# LM358.net
KiCad netlist of a schematic drawn in Altium Designer
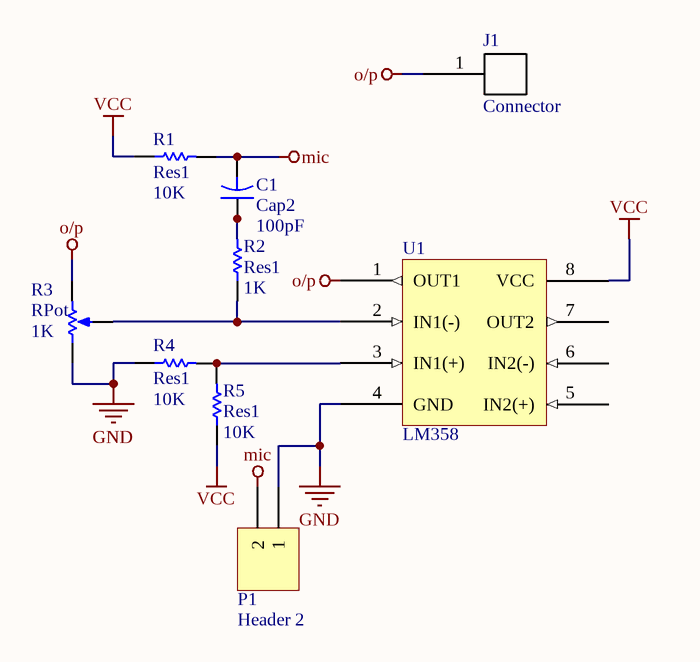
[diagram p0: LM358.SchDoc]

(export (version "E")
  (design (tool "Eeschema 10.0.6"))
  (components
    (comp (ref "C1")
      (value "Cap2")
      (footprint "CAPR5-4X5")
      (description "Capacitor")
      (fields (field (name "ALTIUM_VALUE") "100pF") (field (name "PUBLISHER") "Altium Limited"))
      (libsource (lib "Miscellaneous Devices") (part "Cap2"))
    )
    (comp (ref "J1")
      (value "Connector")
      (footprint "connector")
      (libsource (lib "connector") (part "Connector"))
    )
    (comp (ref "P1")
      (value "Header 2")
      (footprint "HDR1X2")
      (description "Header, 2-Pin")
      (fields (field (name "PUBLISHER") "Altium Limited"))
      (libsource (lib "Miscellaneous Connectors") (part "Header 2"))
    )
    (comp (ref "R1")
      (value "Res1")
      (footprint "AXIAL-0.3")
      (description "Resistor")
      (fields (field (name "ALTIUM_VALUE") "10K") (field (name "PUBLISHER") "Altium Limited"))
      (libsource (lib "Miscellaneous Devices") (part "Res1"))
    )
    (comp (ref "R2")
      (value "Res1")
      (footprint "AXIAL-0.3")
      (description "Resistor")
      (fields (field (name "ALTIUM_VALUE") "1K") (field (name "PUBLISHER") "Altium Limited"))
      (libsource (lib "Miscellaneous Devices") (part "Res1"))
    )
    (comp (ref "R3")
      (value "RPot")
      (footprint "VR5")
      (description "Potentiometer")
      (fields (field (name "ALTIUM_VALUE") "1K") (field (name "PUBLISHER") "Altium Limited"))
      (libsource (lib "Miscellaneous Devices") (part "RPot"))
    )
    (comp (ref "R4")
      (value "Res1")
      (footprint "AXIAL-0.3")
      (description "Resistor")
      (fields (field (name "ALTIUM_VALUE") "10K") (field (name "PUBLISHER") "Altium Limited"))
      (libsource (lib "Miscellaneous Devices") (part "Res1"))
    )
    (comp (ref "R5")
      (value "Res1")
      (footprint "AXIAL-0.3")
      (description "Resistor")
      (fields (field (name "ALTIUM_VALUE") "10K") (field (name "PUBLISHER") "Altium Limited"))
      (libsource (lib "Miscellaneous Devices") (part "Res1"))
    )
    (comp (ref "U1") (value "LM358") (footprint "LM358") (libsource (lib "LM358") (part "LM358")))
  )
  (nets
    (net (code "1") (name "GND") (class "Default")
      (node (ref "P1") (pin "1") (pinfunction "1_1") (pintype "passive"))
      (node (ref "R3") (pin "1") (pinfunction "TOP_1") (pintype "passive"))
      (node (ref "R4") (pin "1") (pinfunction "1_1") (pintype "passive"))
      (node (ref "U1") (pin "4") (pinfunction "GND_4") (pintype "passive"))
    )
    (net (code "2") (name "Net-(C1-Pad1)") (class "Default")
      (node (ref "C1") (pin "1") (pinfunction "1_1") (pintype "passive"))
      (node (ref "R2") (pin "2") (pinfunction "2_2") (pintype "passive"))
    )
    (net (code "3") (name "Net-(R3-TAP)") (class "Default")
      (node (ref "R2") (pin "1") (pinfunction "1_1") (pintype "passive"))
      (node (ref "R3") (pin "3") (pinfunction "TAP_3") (pintype "passive"))
      (node (ref "U1") (pin "2") (pinfunction "IN1(-)_2") (pintype "input"))
    )
    (net (code "4") (name "Net-(U1-IN1(+))") (class "Default")
      (node (ref "R4") (pin "2") (pinfunction "2_2") (pintype "passive"))
      (node (ref "R5") (pin "2") (pinfunction "2_2") (pintype "passive"))
      (node (ref "U1") (pin "3") (pinfunction "IN1(+)_3") (pintype "input"))
    )
    (net (code "5") (name "VCC") (class "Default")
      (node (ref "R1") (pin "1") (pinfunction "1_1") (pintype "passive"))
      (node (ref "R5") (pin "1") (pinfunction "1_1") (pintype "passive"))
      (node (ref "U1") (pin "8") (pinfunction "VCC_8") (pintype "passive"))
    )
    (net (code "6") (name "mic") (class "Default")
      (node (ref "C1") (pin "2") (pinfunction "2_2") (pintype "passive"))
      (node (ref "P1") (pin "2") (pinfunction "2_2") (pintype "passive"))
      (node (ref "R1") (pin "2") (pinfunction "2_2") (pintype "passive"))
    )
    (net (code "7") (name "o{slash}p") (class "Default")
      (node (ref "J1") (pin "1") (pintype "passive"))
      (node (ref "R3") (pin "2") (pinfunction "BOT_2") (pintype "passive"))
      (node (ref "U1") (pin "1") (pinfunction "OUT1_1") (pintype "output"))
    )
    (net (code "8") (name "unconnected-(U1-IN2(+)-Pad5)") (class "Default")
      (node (ref "U1") (pin "5") (pinfunction "IN2(+)_5") (pintype "input"))
    )
    (net (code "9") (name "unconnected-(U1-IN2(-)-Pad6)") (class "Default")
      (node (ref "U1") (pin "6") (pinfunction "IN2(-)_6") (pintype "input"))
    )
    (net (code "10") (name "unconnected-(U1-OUT2-Pad7)") (class "Default")
      (node (ref "U1") (pin "7") (pinfunction "OUT2_7") (pintype "output"))
    )
  )
)
